# PCB-schematic-v1.net
KiCad netlist of a schematic drawn in EAGLE
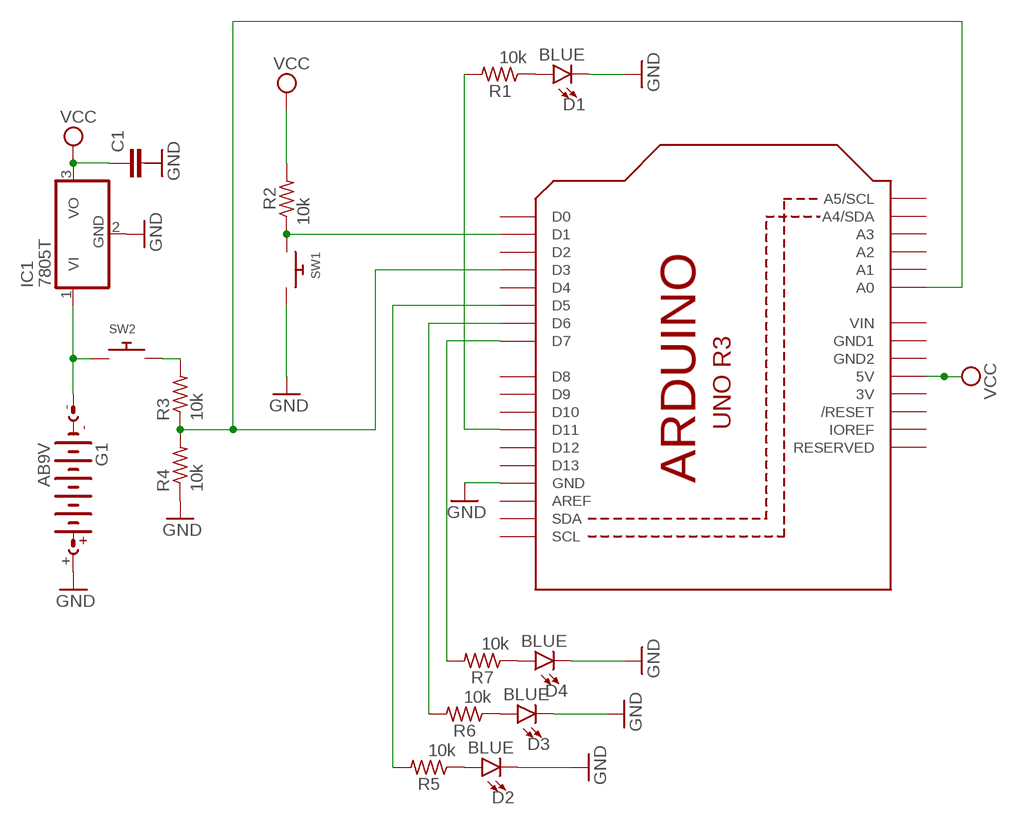
[diagram p0: schematic, sheet 1]

(export (version "E")
  (design (tool "Eeschema 10.0.6"))
  (components
    (comp (ref "C1")
      (value "C10/5")
      (footprint "eagle-import:C10B5")
      (libsource (lib "eagle-import") (part "C10/5"))
    )
    (comp (ref "D1")
      (value "BLUE")
      (footprint "eagle-import:LED-1206")
      (libsource (lib "eagle-import") (part "LED-BLUE1206"))
    )
    (comp (ref "D2")
      (value "BLUE")
      (footprint "eagle-import:LED-1206")
      (libsource (lib "eagle-import") (part "LED-BLUE1206"))
    )
    (comp (ref "D3")
      (value "BLUE")
      (footprint "eagle-import:LED-1206")
      (libsource (lib "eagle-import") (part "LED-BLUE1206"))
    )
    (comp (ref "D4")
      (value "BLUE")
      (footprint "eagle-import:LED-1206")
      (libsource (lib "eagle-import") (part "LED-BLUE1206"))
    )
    (comp (ref "G1")
      (value "AB9V")
      (footprint "eagle-import:AB9V")
      (libsource (lib "eagle-import") (part "AB9V"))
    )
    (comp (ref "IC1")
      (value "7805T")
      (footprint "eagle-import:TO220H")
      (libsource (lib "eagle-import") (part "78T05"))
    )
    (comp (ref "R1")
      (value "10k")
      (footprint "eagle-import:R0805")
      (libsource (lib "eagle-import") (part "R-US_R0805"))
    )
    (comp (ref "R2")
      (value "10k")
      (footprint "eagle-import:R0805")
      (libsource (lib "eagle-import") (part "R-US_R0805"))
    )
    (comp (ref "R3")
      (value "10k")
      (footprint "eagle-import:R0805")
      (libsource (lib "eagle-import") (part "R-US_R0805"))
    )
    (comp (ref "R4")
      (value "10k")
      (footprint "eagle-import:R0805")
      (libsource (lib "eagle-import") (part "R-US_R0805"))
    )
    (comp (ref "R5")
      (value "10k")
      (footprint "eagle-import:R0805")
      (libsource (lib "eagle-import") (part "R-US_R0805"))
    )
    (comp (ref "R6")
      (value "10k")
      (footprint "eagle-import:R0805")
      (libsource (lib "eagle-import") (part "R-US_R0805"))
    )
    (comp (ref "R7")
      (value "10k")
      (footprint "eagle-import:R0805")
      (libsource (lib "eagle-import") (part "R-US_R0805"))
    )
    (comp (ref "SW1")
      (value "SWITCH_PUSHBUTTONSOFTTOUCHSMD_SJ")
      (footprint "eagle-import:PUSHBUTTON_SMD_SJ")
      (libsource (lib "eagle-import") (part "SWITCH_PUSHBUTTONSOFTTOUCHSMD_SJ"))
    )
    (comp (ref "SW2")
      (value "SWITCH_PUSHBUTTONSOFTTOUCHSMD_SJ")
      (footprint "eagle-import:PUSHBUTTON_SMD_SJ")
      (libsource (lib "eagle-import") (part "SWITCH_PUSHBUTTONSOFTTOUCHSMD_SJ"))
    )
    (comp (ref "U1")
      (value "ARDUINOR3-BPLACE")
      (footprint "eagle-import:ARDUINOR3-BPLACE")
      (libsource (lib "eagle-import") (part "ARDUINOR3-BPLACE"))
    )
  )
  (nets
    (net (code "1") (name "/3V") (class "Default")
      (node (ref "U1") (pin "3V") (pinfunction "3V_3V") (pintype "power_in"))
    )
    (net (code "2") (name "/GND1") (class "Default")
      (node (ref "U1") (pin "GND1") (pinfunction "GND1_GND1") (pintype "power_in"))
    )
    (net (code "3") (name "/GND2") (class "Default")
      (node (ref "U1") (pin "GND2") (pinfunction "GND2_GND2") (pintype "power_in"))
    )
    (net (code "4") (name "/VIN") (class "Default")
      (node (ref "U1") (pin "VIN") (pinfunction "VIN_VIN") (pintype "power_in"))
    )
    (net (code "5") (name "GND") (class "Default")
      (node (ref "D1") (pin "C") (pinfunction "C_C") (pintype "passive"))
      (node (ref "D2") (pin "C") (pinfunction "C_C") (pintype "passive"))
      (node (ref "D3") (pin "C") (pinfunction "C_C") (pintype "passive"))
      (node (ref "D4") (pin "C") (pinfunction "C_C") (pintype "passive"))
      (node (ref "G1") (pin "+") (pinfunction "+_+") (pintype "passive"))
      (node (ref "IC1") (pin "2") (pinfunction "GND_2") (pintype "passive"))
      (node (ref "R4") (pin "1") (pinfunction "1_1") (pintype "passive"))
      (node (ref "SW1") (pin "P$2") (pinfunction "P$2_P$2") (pintype "passive"))
      (node (ref "U1") (pin "GND") (pinfunction "GND_GND") (pintype "power_in"))
    )
    (net (code "6") (name "Net-(D1-PadA)") (class "Default")
      (node (ref "D1") (pin "A") (pinfunction "A_A") (pintype "passive"))
      (node (ref "R1") (pin "1") (pinfunction "1_1") (pintype "passive"))
    )
    (net (code "7") (name "Net-(D2-PadA)") (class "Default")
      (node (ref "D2") (pin "A") (pinfunction "A_A") (pintype "passive"))
      (node (ref "R5") (pin "1") (pinfunction "1_1") (pintype "passive"))
    )
    (net (code "8") (name "Net-(D3-PadA)") (class "Default")
      (node (ref "D3") (pin "A") (pinfunction "A_A") (pintype "passive"))
      (node (ref "R6") (pin "1") (pinfunction "1_1") (pintype "passive"))
    )
    (net (code "9") (name "Net-(D4-PadA)") (class "Default")
      (node (ref "D4") (pin "A") (pinfunction "A_A") (pintype "passive"))
      (node (ref "R7") (pin "1") (pinfunction "1_1") (pintype "passive"))
    )
    (net (code "10") (name "Net-(IC1-VI)") (class "Default")
      (node (ref "G1") (pin "-") (pinfunction "-_-") (pintype "passive"))
      (node (ref "IC1") (pin "1") (pinfunction "VI_1") (pintype "input"))
      (node (ref "SW2") (pin "P$1") (pinfunction "P$1_P$1") (pintype "passive"))
    )
    (net (code "11") (name "Net-(R1-Pad2)") (class "Default")
      (node (ref "R1") (pin "2") (pinfunction "2_2") (pintype "passive"))
      (node (ref "U1") (pin "D11") (pinfunction "D11_D11") (pintype "bidirectional"))
    )
    (net (code "12") (name "Net-(R2-Pad1)") (class "Default")
      (node (ref "R2") (pin "1") (pinfunction "1_1") (pintype "passive"))
      (node (ref "SW1") (pin "P$1") (pinfunction "P$1_P$1") (pintype "passive"))
      (node (ref "U1") (pin "D1") (pinfunction "D1_D1") (pintype "bidirectional"))
    )
    (net (code "13") (name "Net-(R3-Pad1)") (class "Default")
      (node (ref "R3") (pin "1") (pinfunction "1_1") (pintype "passive"))
      (node (ref "R4") (pin "2") (pinfunction "2_2") (pintype "passive"))
      (node (ref "U1") (pin "A0") (pinfunction "A0_A0") (pintype "bidirectional"))
      (node (ref "U1") (pin "D3") (pinfunction "D3_D3") (pintype "bidirectional"))
    )
    (net (code "14") (name "Net-(R3-Pad2)") (class "Default")
      (node (ref "R3") (pin "2") (pinfunction "2_2") (pintype "passive"))
      (node (ref "SW2") (pin "P$2") (pinfunction "P$2_P$2") (pintype "passive"))
    )
    (net (code "15") (name "Net-(R5-Pad2)") (class "Default")
      (node (ref "R5") (pin "2") (pinfunction "2_2") (pintype "passive"))
      (node (ref "U1") (pin "D5") (pinfunction "D5_D5") (pintype "bidirectional"))
    )
    (net (code "16") (name "Net-(R6-Pad2)") (class "Default")
      (node (ref "R6") (pin "2") (pinfunction "2_2") (pintype "passive"))
      (node (ref "U1") (pin "D6") (pinfunction "D6_D6") (pintype "bidirectional"))
    )
    (net (code "17") (name "Net-(R7-Pad2)") (class "Default")
      (node (ref "R7") (pin "2") (pinfunction "2_2") (pintype "passive"))
      (node (ref "U1") (pin "D7") (pinfunction "D7_D7") (pintype "bidirectional"))
    )
    (net (code "18") (name "VCC") (class "Default")
      (node (ref "C1") (pin "1") (pinfunction "1_1") (pintype "passive"))
      (node (ref "IC1") (pin "3") (pinfunction "VO_3") (pintype "passive"))
      (node (ref "R2") (pin "2") (pinfunction "2_2") (pintype "passive"))
      (node (ref "U1") (pin "5V") (pinfunction "5V_5V") (pintype "power_in"))
    )
    (net (code "19") (name "unconnected-(C1-Pad2)") (class "Default")
      (node (ref "C1") (pin "2") (pinfunction "2_2") (pintype "passive"))
    )
    (net (code "20") (name "unconnected-(U1-A4{slash}SDA-PadA4)") (class "Default")
      (node (ref "U1") (pin "A4") (pinfunction "A4/SDA_A4") (pintype "bidirectional"))
    )
    (net (code "21") (name "unconnected-(U1-A5{slash}SCL-PadA5)") (class "Default")
      (node (ref "U1") (pin "A5") (pinfunction "A5/SCL_A5") (pintype "bidirectional"))
    )
    (net (code "22") (name "unconnected-(U1-PadA1)") (class "Default")
      (node (ref "U1") (pin "A1") (pinfunction "A1_A1") (pintype "bidirectional"))
    )
    (net (code "23") (name "unconnected-(U1-PadA2)") (class "Default")
      (node (ref "U1") (pin "A2") (pinfunction "A2_A2") (pintype "bidirectional"))
    )
    (net (code "24") (name "unconnected-(U1-PadA3)") (class "Default")
      (node (ref "U1") (pin "A3") (pinfunction "A3_A3") (pintype "bidirectional"))
    )
    (net (code "25") (name "unconnected-(U1-PadAREF)") (class "Default")
      (node (ref "U1") (pin "AREF") (pinfunction "AREF_AREF") (pintype "bidirectional"))
    )
    (net (code "26") (name "unconnected-(U1-PadD0)") (class "Default")
      (node (ref "U1") (pin "D0") (pinfunction "D0_D0") (pintype "bidirectional"))
    )
    (net (code "27") (name "unconnected-(U1-PadD2)") (class "Default")
      (node (ref "U1") (pin "D2") (pinfunction "D2_D2") (pintype "bidirectional"))
    )
    (net (code "28") (name "unconnected-(U1-PadD4)") (class "Default")
      (node (ref "U1") (pin "D4") (pinfunction "D4_D4") (pintype "bidirectional"))
    )
    (net (code "29") (name "unconnected-(U1-PadD8)") (class "Default")
      (node (ref "U1") (pin "D8") (pinfunction "D8_D8") (pintype "bidirectional"))
    )
    (net (code "30") (name "unconnected-(U1-PadD9)") (class "Default")
      (node (ref "U1") (pin "D9") (pinfunction "D9_D9") (pintype "bidirectional"))
    )
    (net (code "31") (name "unconnected-(U1-PadD10)") (class "Default")
      (node (ref "U1") (pin "D10") (pinfunction "D10_D10") (pintype "bidirectional"))
    )
    (net (code "32") (name "unconnected-(U1-PadD12)") (class "Default")
      (node (ref "U1") (pin "D12") (pinfunction "D12_D12") (pintype "bidirectional"))
    )
    (net (code "33") (name "unconnected-(U1-PadD13)") (class "Default")
      (node (ref "U1") (pin "D13") (pinfunction "D13_D13") (pintype "bidirectional"))
    )
    (net (code "34") (name "unconnected-(U1-PadIOREF)") (class "Default")
      (node (ref "U1") (pin "IOREF") (pinfunction "IOREF_IOREF") (pintype "output"))
    )
    (net (code "35") (name "unconnected-(U1-PadRESERVED)") (class "Default")
      (node (ref "U1") (pin "RESERVED") (pinfunction "RESERVED_RESERVED") (pintype "no_connect"))
    )
    (net (code "36") (name "unconnected-(U1-PadSCL)") (class "Default")
      (node (ref "U1") (pin "SCL") (pinfunction "SCL_SCL") (pintype "bidirectional"))
    )
    (net (code "37") (name "unconnected-(U1-PadSDA)") (class "Default")
      (node (ref "U1") (pin "SDA") (pinfunction "SDA_SDA") (pintype "bidirectional"))
    )
    (net (code "38") (name "unconnected-(U1-{slash}RESET-PadRESET)") (class "Default")
      (node (ref "U1") (pin "RESET") (pinfunction "/RESET_RESET") (pintype "bidirectional"))
    )
  )
)
